# eBox_LCD.net
KiCad netlist of a schematic drawn in Altium Designer
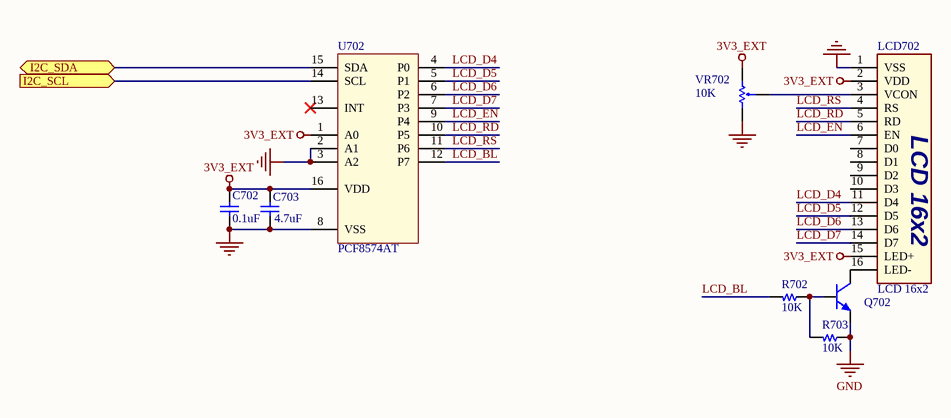
[diagram p0: eBox_LCD.SchDoc]

(export (version "E")
  (design (tool "Eeschema 10.0.6"))
  (components
    (comp (ref "C702")
      (value "0.1uF")
      (footprint "C 0603")
      (description "CAP CER 0.1UF 50V X7R 0603")
      (libsource (lib "chipfc_altium_libs") (part "Capacitor NP"))
    )
    (comp (ref "C703")
      (value "4.7uF")
      (footprint "C 0603")
      (description "CAP CER 4.7UF 50V X7R 0603")
      (libsource (lib "chipfc_altium_libs") (part "Capacitor NP"))
    )
    (comp (ref "LCD702")
      (value "LCD 16x2")
      (footprint "LCD 1602A")
      (description "Character LCD 16x2")
      (libsource (lib "chipfc_altium_libs") (part "LCD 16x2"))
    )
    (comp (ref "Q702")
      (value "MMBT3904LT1G")
      (footprint "SOT-23")
      (description "TRANS NPN 40V 0.2A SOT23")
      (libsource (lib "chipfc_altium_libs") (part "Transistor NPN"))
    )
    (comp (ref "R702")
      (value "10K")
      (footprint "R 0603")
      (description "RES SMD 10K OHM 1% 1/10W 0603")
      (libsource (lib "chipfc_altium_libs") (part "Resistor"))
    )
    (comp (ref "R703")
      (value "10K")
      (footprint "R 0603")
      (description "RES SMD 10K OHM 1% 1/10W 0603")
      (libsource (lib "chipfc_altium_libs") (part "Resistor"))
    )
    (comp (ref "U702")
      (value "PCF8574AT")
      (footprint "SO16/PCF8574AT")
      (description "Remote 8-bit I/O expander for I2C-bus with interrupt")
      (fields (field (name "PART NO") "PCF8574AT/3"))
      (libsource (lib "chipfc_altium_libs") (part "PCF8574AT"))
    )
    (comp (ref "VR702")
      (value "10K")
      (footprint "R VAR A 3D")
      (description "TRIMMER 10K OHM 0.5W PC PIN")
      (libsource (lib "chipfc_altium_libs") (part "Resistor Variable"))
    )
  )
  (nets
    (net (code "1") (name "/I2C_SCL") (class "Default")
      (node (ref "U702") (pin "14") (pinfunction "SCL_14") (pintype "passive"))
    )
    (net (code "2") (name "/I2C_SDA") (class "Default")
      (node (ref "U702") (pin "15") (pinfunction "SDA_15") (pintype "passive"))
    )
    (net (code "3") (name "/LCD_BL") (class "Default")
      (node (ref "R702") (pin "2") (pinfunction "2_2") (pintype "passive"))
      (node (ref "U702") (pin "12") (pinfunction "P7_12") (pintype "passive"))
    )
    (net (code "4") (name "/LCD_D4") (class "Default")
      (node (ref "LCD702") (pin "11") (pinfunction "D4_11") (pintype "passive"))
      (node (ref "U702") (pin "4") (pinfunction "P0_4") (pintype "passive"))
    )
    (net (code "5") (name "/LCD_D5") (class "Default")
      (node (ref "LCD702") (pin "12") (pinfunction "D5_12") (pintype "passive"))
      (node (ref "U702") (pin "5") (pinfunction "P1_5") (pintype "passive"))
    )
    (net (code "6") (name "/LCD_D6") (class "Default")
      (node (ref "LCD702") (pin "13") (pinfunction "D6_13") (pintype "passive"))
      (node (ref "U702") (pin "6") (pinfunction "P2_6") (pintype "passive"))
    )
    (net (code "7") (name "/LCD_D7") (class "Default")
      (node (ref "LCD702") (pin "14") (pinfunction "D7_14") (pintype "passive"))
      (node (ref "U702") (pin "7") (pinfunction "P3_7") (pintype "passive"))
    )
    (net (code "8") (name "/LCD_EN") (class "Default")
      (node (ref "LCD702") (pin "6") (pinfunction "EN_6") (pintype "passive"))
      (node (ref "U702") (pin "9") (pinfunction "P4_9") (pintype "passive"))
    )
    (net (code "9") (name "/LCD_RD") (class "Default")
      (node (ref "LCD702") (pin "5") (pinfunction "RD_5") (pintype "passive"))
      (node (ref "U702") (pin "10") (pinfunction "P5_10") (pintype "passive"))
    )
    (net (code "10") (name "/LCD_RS") (class "Default")
      (node (ref "LCD702") (pin "4") (pinfunction "RS_4") (pintype "passive"))
      (node (ref "U702") (pin "11") (pinfunction "P6_11") (pintype "passive"))
    )
    (net (code "11") (name "3V3_EXT") (class "Default")
      (node (ref "C702") (pin "1") (pinfunction "1_1") (pintype "passive"))
      (node (ref "C703") (pin "1") (pinfunction "1_1") (pintype "passive"))
      (node (ref "LCD702") (pin "15") (pinfunction "LED+_15") (pintype "passive"))
      (node (ref "LCD702") (pin "2") (pinfunction "VDD_2") (pintype "passive"))
      (node (ref "U702") (pin "1") (pinfunction "A0_1") (pintype "passive"))
      (node (ref "U702") (pin "16") (pinfunction "VDD_16") (pintype "passive"))
      (node (ref "VR702") (pin "1") (pinfunction "1_1") (pintype "passive"))
    )
    (net (code "12") (name "GND") (class "Default")
      (node (ref "C702") (pin "2") (pinfunction "2_2") (pintype "passive"))
      (node (ref "C703") (pin "2") (pinfunction "2_2") (pintype "passive"))
      (node (ref "LCD702") (pin "1") (pinfunction "VSS_1") (pintype "passive"))
      (node (ref "Q702") (pin "2") (pinfunction "E_2") (pintype "passive"))
      (node (ref "R703") (pin "1") (pinfunction "1_1") (pintype "passive"))
      (node (ref "U702") (pin "2") (pinfunction "A1_2") (pintype "passive"))
      (node (ref "U702") (pin "3") (pinfunction "A2_3") (pintype "passive"))
      (node (ref "U702") (pin "8") (pinfunction "VSS_8") (pintype "passive"))
      (node (ref "VR702") (pin "3") (pinfunction "3_3") (pintype "passive"))
    )
    (net (code "13") (name "Net-(LCD702-LED-)") (class "Default")
      (node (ref "LCD702") (pin "16") (pinfunction "LED-_16") (pintype "passive"))
      (node (ref "Q702") (pin "3") (pinfunction "C_3") (pintype "passive"))
    )
    (net (code "14") (name "Net-(LCD702-VCON)") (class "Default")
      (node (ref "LCD702") (pin "3") (pinfunction "VCON_3") (pintype "passive"))
      (node (ref "VR702") (pin "2") (pinfunction "2_2") (pintype "passive"))
    )
    (net (code "15") (name "Net-(Q702-B)") (class "Default")
      (node (ref "Q702") (pin "1") (pinfunction "B_1") (pintype "passive"))
      (node (ref "R702") (pin "1") (pinfunction "1_1") (pintype "passive"))
      (node (ref "R703") (pin "2") (pinfunction "2_2") (pintype "passive"))
    )
    (net (code "16") (name "unconnected-(LCD702-D0-Pad7)") (class "Default")
      (node (ref "LCD702") (pin "7") (pinfunction "D0_7") (pintype "passive"))
    )
    (net (code "17") (name "unconnected-(LCD702-D1-Pad8)") (class "Default")
      (node (ref "LCD702") (pin "8") (pinfunction "D1_8") (pintype "passive"))
    )
    (net (code "18") (name "unconnected-(LCD702-D2-Pad9)") (class "Default")
      (node (ref "LCD702") (pin "9") (pinfunction "D2_9") (pintype "passive"))
    )
    (net (code "19") (name "unconnected-(LCD702-D3-Pad10)") (class "Default")
      (node (ref "LCD702") (pin "10") (pinfunction "D3_10") (pintype "passive"))
    )
    (net (code "20") (name "unconnected-(U702-INT-Pad13)") (class "Default")
      (node (ref "U702") (pin "13") (pinfunction "INT_13") (pintype "passive+no_connect"))
    )
  )
)
